# LIDO-HW_400_AccessoryInterfaces.net
KiCad netlist of a schematic drawn in Altium Designer
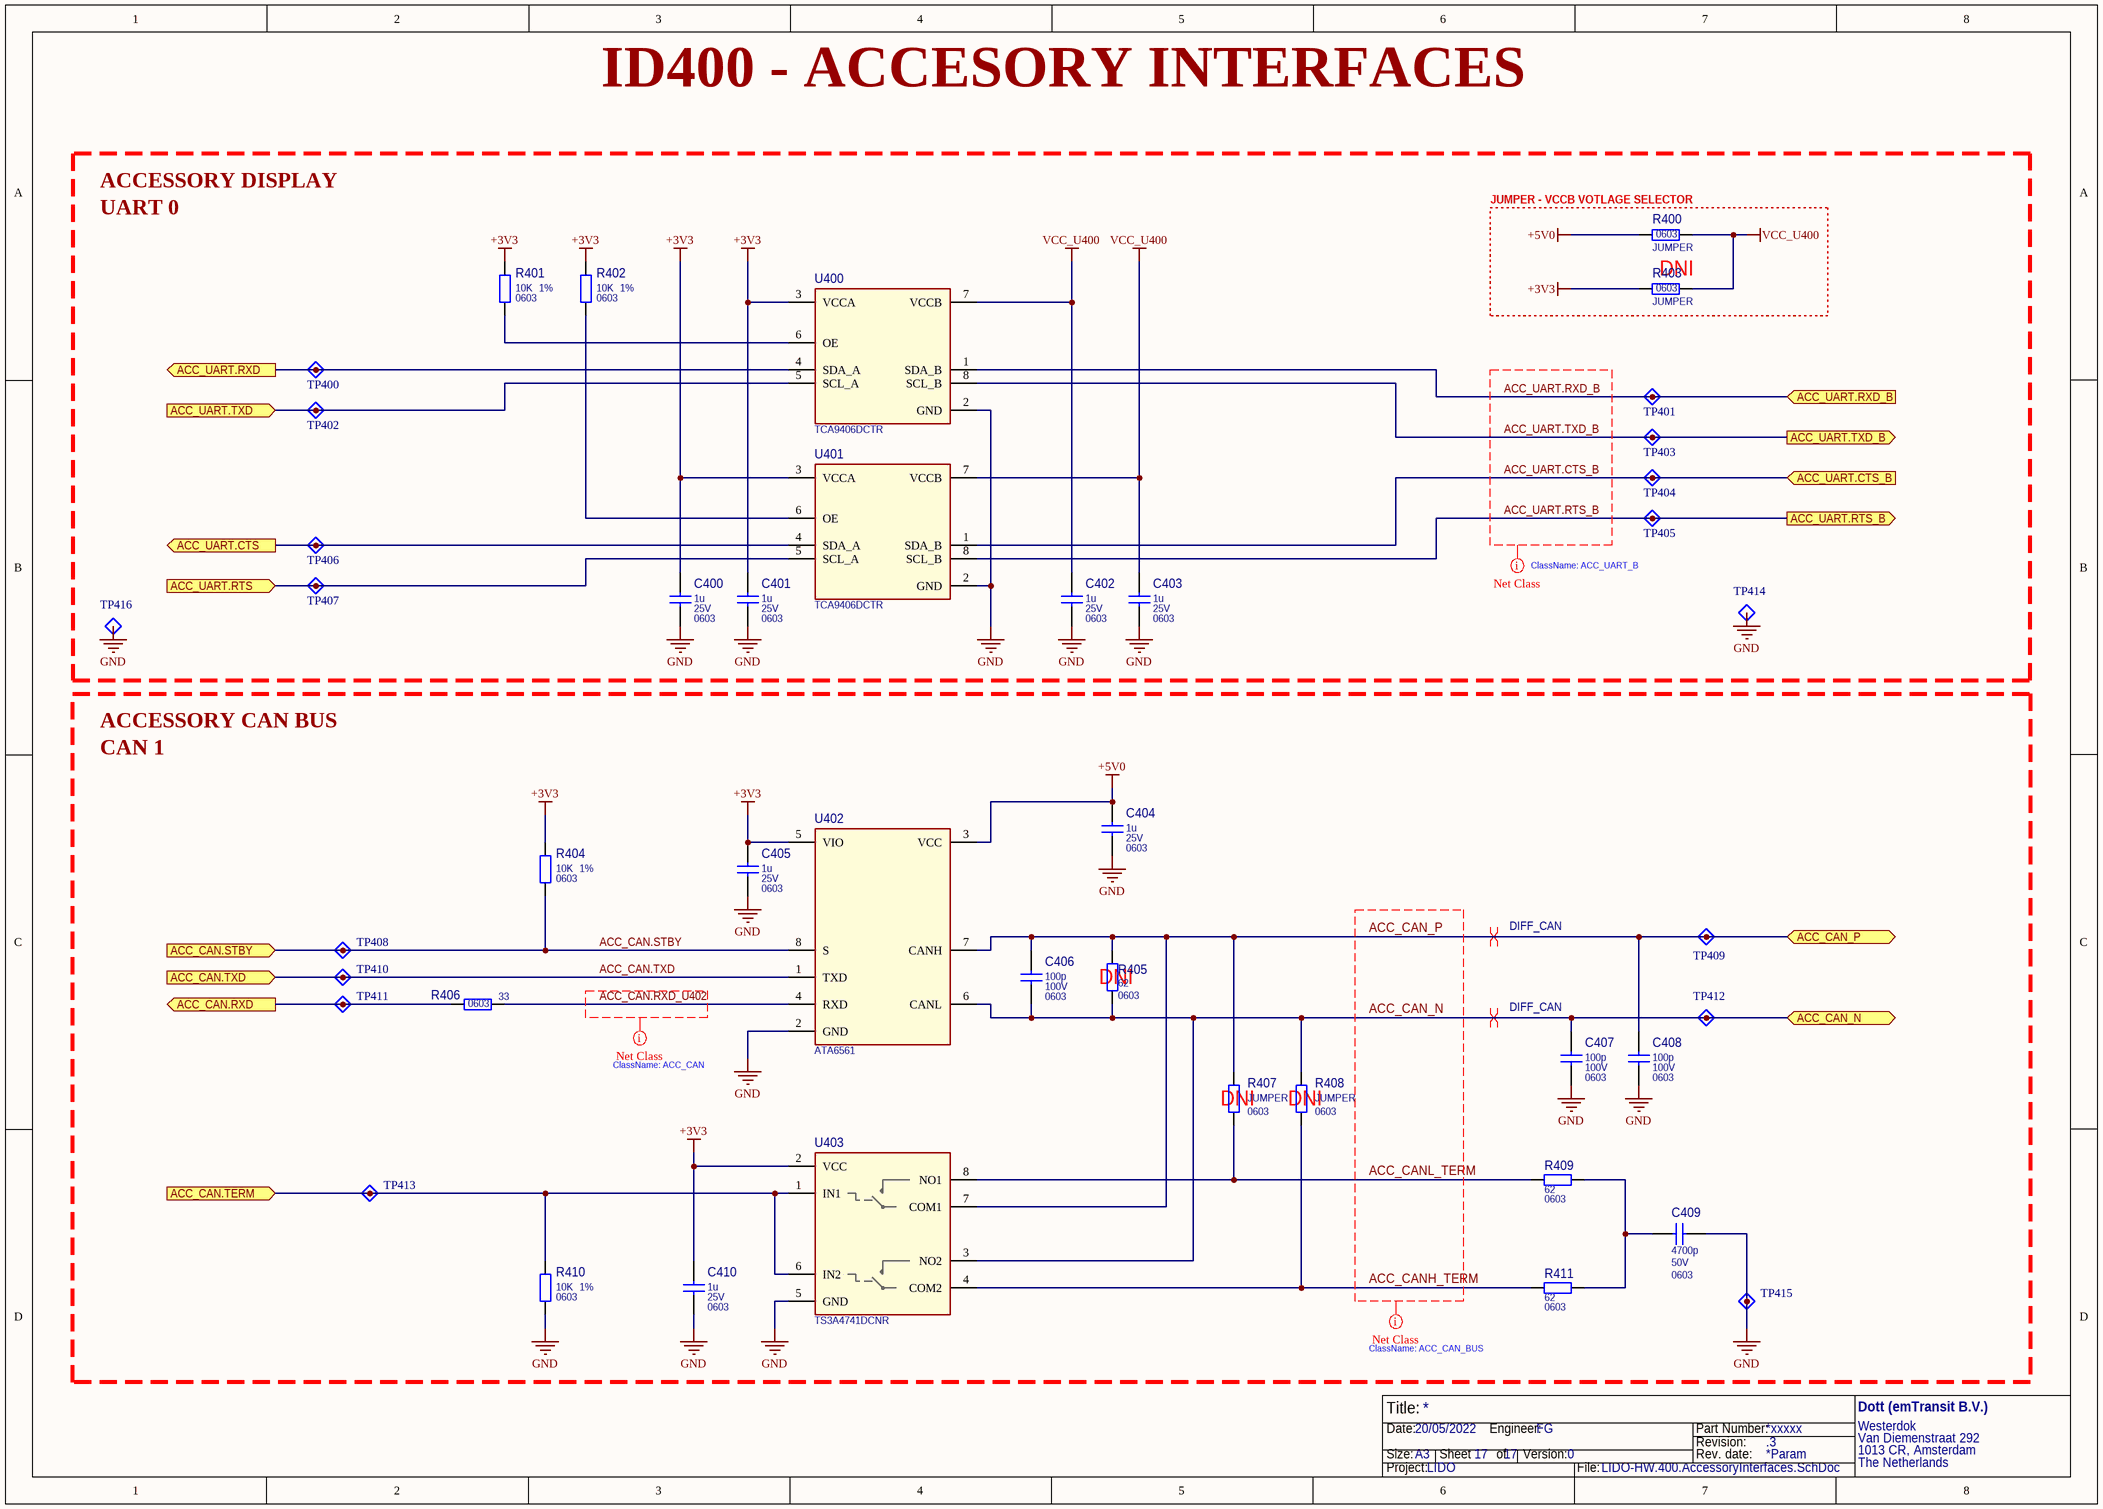
[diagram p0: LIDO-HW.400.AccessoryInterfaces.SchDoc]

(export (version "E")
  (design (tool "Eeschema 10.0.6"))
  (components
    (comp (ref "C400")
      (value "1u")
      (footprint "CAP_0603_1608X90-N_MURATA_A")
      (description "CAP CER 1UF 25V X7R 0603")
      (fields
        (field (name "MANUFACTURER PART NUMBER") "CGA3E1X7R1E105M080AE")
        (field (name "MANUFACTURER") "TDK Corporation")
        (field (name "PART VALUE 2") "25V")
        (field (name "PART PACKAGE") "0603")
      )
      (libsource (lib "DB_Library") (part "Ceramic"))
    )
    (comp (ref "C401")
      (value "1u")
      (footprint "CAP_0603_1608X90-N_MURATA_A")
      (description "CAP CER 1UF 25V X7R 0603")
      (fields
        (field (name "MANUFACTURER PART NUMBER") "CGA3E1X7R1E105M080AE")
        (field (name "MANUFACTURER") "TDK Corporation")
        (field (name "PART VALUE 2") "25V")
        (field (name "PART PACKAGE") "0603")
      )
      (libsource (lib "DB_Library") (part "Ceramic"))
    )
    (comp (ref "C402")
      (value "1u")
      (footprint "CAP_0603_1608X90-N_MURATA_A")
      (description "CAP CER 1UF 25V X7R 0603")
      (fields
        (field (name "MANUFACTURER PART NUMBER") "CGA3E1X7R1E105M080AE")
        (field (name "MANUFACTURER") "TDK Corporation")
        (field (name "PART VALUE 2") "25V")
        (field (name "PART PACKAGE") "0603")
      )
      (libsource (lib "DB_Library") (part "Ceramic"))
    )
    (comp (ref "C403")
      (value "1u")
      (footprint "CAP_0603_1608X90-N_MURATA_A")
      (description "CAP CER 1UF 25V X7R 0603")
      (fields
        (field (name "MANUFACTURER PART NUMBER") "CGA3E1X7R1E105M080AE")
        (field (name "MANUFACTURER") "TDK Corporation")
        (field (name "PART VALUE 2") "25V")
        (field (name "PART PACKAGE") "0603")
      )
      (libsource (lib "DB_Library") (part "Ceramic"))
    )
    (comp (ref "C404")
      (value "1u")
      (footprint "CAP_0603_1608X90-N_MURATA_A")
      (description "CAP CER 1UF 25V X7R 0603")
      (fields
        (field (name "MANUFACTURER PART NUMBER") "CGA3E1X7R1E105M080AE")
        (field (name "MANUFACTURER") "TDK Corporation")
        (field (name "PART VALUE 2") "25V")
        (field (name "PART PACKAGE") "0603")
      )
      (libsource (lib "DB_Library") (part "Ceramic"))
    )
    (comp (ref "C405")
      (value "1u")
      (footprint "CAP_0603_1608X90-N_MURATA_A")
      (description "CAP CER 1UF 25V X7R 0603")
      (fields
        (field (name "MANUFACTURER PART NUMBER") "CGA3E1X7R1E105M080AE")
        (field (name "MANUFACTURER") "TDK Corporation")
        (field (name "PART VALUE 2") "25V")
        (field (name "PART PACKAGE") "0603")
      )
      (libsource (lib "DB_Library") (part "Ceramic"))
    )
    (comp (ref "C406")
      (value "100p")
      (footprint "CAP_0603_1608X90-N_MURATA_A")
      (description "CAP CER 100PF 100V C0G 0603")
      (fields
        (field (name "MANUFACTURER PART NUMBER") "CGA3E2C0G2A101J080AA")
        (field (name "MANUFACTURER") "TDK Corporation")
        (field (name "PART VALUE 2") "100V")
        (field (name "PART PACKAGE") "0603")
      )
      (libsource (lib "DB_Library") (part "Ceramic"))
    )
    (comp (ref "C407")
      (value "100p")
      (footprint "CAP_0603_1608X90-N_MURATA_A")
      (description "CAP CER 100PF 100V C0G 0603")
      (fields
        (field (name "MANUFACTURER PART NUMBER") "CGA3E2C0G2A101J080AA")
        (field (name "MANUFACTURER") "TDK Corporation")
        (field (name "PART VALUE 2") "100V")
        (field (name "PART PACKAGE") "0603")
      )
      (libsource (lib "DB_Library") (part "Ceramic"))
    )
    (comp (ref "C408")
      (value "100p")
      (footprint "CAP_0603_1608X90-N_MURATA_A")
      (description "CAP CER 100PF 100V C0G 0603")
      (fields
        (field (name "MANUFACTURER PART NUMBER") "CGA3E2C0G2A101J080AA")
        (field (name "MANUFACTURER") "TDK Corporation")
        (field (name "PART VALUE 2") "100V")
        (field (name "PART PACKAGE") "0603")
      )
      (libsource (lib "DB_Library") (part "Ceramic"))
    )
    (comp (ref "C409")
      (value "4700p")
      (footprint "CAP_0603_1608X90-N_MURATA_A")
      (description "CAP CER 4700PF 50V X7R 0603")
      (fields
        (field (name "MANUFACTURER PART NUMBER") "CGA3E2X7R1H472K080AA")
        (field (name "MANUFACTURER") "TDK Corporation")
        (field (name "PART VALUE 2") "50V")
        (field (name "PART PACKAGE") "0603")
      )
      (libsource (lib "DB_Library") (part "Ceramic"))
    )
    (comp (ref "C410")
      (value "1u")
      (footprint "CAP_0603_1608X90-N_MURATA_A")
      (description "CAP CER 1UF 25V X7R 0603")
      (fields
        (field (name "MANUFACTURER PART NUMBER") "CGA3E1X7R1E105M080AE")
        (field (name "MANUFACTURER") "TDK Corporation")
        (field (name "PART VALUE 2") "25V")
        (field (name "PART PACKAGE") "0603")
      )
      (libsource (lib "DB_Library") (part "Ceramic"))
    )
    (comp (ref "R400")
      (value "JUMPER")
      (footprint "RES_0603_1608X60-N_YAGEO_A")
      (description "RES 0 OHM JUMPER 1/10W 0603")
      (fields
        (field (name "MANUFACTURER PART NUMBER") "RC0603JR-070RL")
        (field (name "MANUFACTURER") "YAGEO")
        (field (name "PART PACKAGE") "0603")
      )
      (libsource (lib "") (part "Resistor_1"))
    )
    (comp (ref "R401")
      (value "10K")
      (footprint "RES_0603_1608X60-N_YAGEO_A")
      (description "RES 10K OHM 1% 1/10W 0603")
      (fields
        (field (name "MANUFACTURER PART NUMBER") "RC0603FR-0710KL")
        (field (name "MANUFACTURER") "YAGEO")
        (field (name "PART VALUE 2") "1%")
        (field (name "PART PACKAGE") "0603")
      )
      (libsource (lib "DB_Library") (part "Resistor"))
    )
    (comp (ref "R402")
      (value "10K")
      (footprint "RES_0603_1608X60-N_YAGEO_A")
      (description "RES 10K OHM 1% 1/10W 0603")
      (fields
        (field (name "MANUFACTURER PART NUMBER") "RC0603FR-0710KL")
        (field (name "MANUFACTURER") "YAGEO")
        (field (name "PART VALUE 2") "1%")
        (field (name "PART PACKAGE") "0603")
      )
      (libsource (lib "DB_Library") (part "Resistor"))
    )
    (comp (ref "R403")
      (value "JUMPER")
      (footprint "RES_0603_1608X60-N_YAGEO_A")
      (description "RES 0 OHM JUMPER 1/10W 0603")
      (fields
        (field (name "MANUFACTURER PART NUMBER") "RC0603JR-070RL")
        (field (name "MANUFACTURER") "YAGEO")
        (field (name "PART PACKAGE") "0603")
      )
      (libsource (lib "") (part "Resistor_1"))
    )
    (comp (ref "R404")
      (value "10K")
      (footprint "RES_0603_1608X60-N_YAGEO_A")
      (description "RES 10K OHM 1% 1/10W 0603")
      (fields
        (field (name "MANUFACTURER PART NUMBER") "RC0603FR-0710KL")
        (field (name "MANUFACTURER") "YAGEO")
        (field (name "PART VALUE 2") "1%")
        (field (name "PART PACKAGE") "0603")
      )
      (libsource (lib "DB_Library") (part "Resistor"))
    )
    (comp (ref "R405")
      (value "62")
      (footprint "RES_0603_1608X60-N_YAGEO_A")
      (description "RES SMD 62 OHM 1% 1/10W 0603")
      (fields
        (field (name "MANUFACTURER PART NUMBER") "ERJ-3EKF62R0V")
        (field (name "MANUFACTURER") "Panasonic Electronic Components")
        (field (name "PART PACKAGE") "0603")
      )
      (libsource (lib "DB_Library") (part "Resistor"))
    )
    (comp (ref "R406")
      (value "33")
      (footprint "RES_0603_1608X60-N_YAGEO_A")
      (description "RES 33 OHM 5% 1/10W 0603")
      (fields
        (field (name "MANUFACTURER PART NUMBER") "RC0603JR-0733RL")
        (field (name "MANUFACTURER") "YAGEO")
        (field (name "PART PACKAGE") "0603")
      )
      (libsource (lib "") (part "Resistor_1"))
    )
    (comp (ref "R407")
      (value "JUMPER")
      (footprint "RES_0603_1608X60-N_YAGEO_A")
      (description "RES 0 OHM JUMPER 1/10W 0603")
      (fields
        (field (name "MANUFACTURER PART NUMBER") "RC0603JR-070RL")
        (field (name "MANUFACTURER") "YAGEO")
        (field (name "PART PACKAGE") "0603")
      )
      (libsource (lib "DB_Library") (part "Resistor"))
    )
    (comp (ref "R408")
      (value "JUMPER")
      (footprint "RES_0603_1608X60-N_YAGEO_A")
      (description "RES 0 OHM JUMPER 1/10W 0603")
      (fields
        (field (name "MANUFACTURER PART NUMBER") "RC0603JR-070RL")
        (field (name "MANUFACTURER") "YAGEO")
        (field (name "PART PACKAGE") "0603")
      )
      (libsource (lib "DB_Library") (part "Resistor"))
    )
    (comp (ref "R409")
      (value "62")
      (footprint "RES_0603_1608X60-N_YAGEO_A")
      (description "RES SMD 62 OHM 1% 1/10W 0603")
      (fields
        (field (name "MANUFACTURER PART NUMBER") "ERJ-3EKF62R0V")
        (field (name "MANUFACTURER") "Panasonic Electronic Components")
        (field (name "PART PACKAGE") "0603")
      )
      (libsource (lib "") (part "Resistor_1"))
    )
    (comp (ref "R410")
      (value "10K")
      (footprint "RES_0603_1608X60-N_YAGEO_A")
      (description "RES 10K OHM 1% 1/10W 0603")
      (fields
        (field (name "MANUFACTURER PART NUMBER") "RC0603FR-0710KL")
        (field (name "MANUFACTURER") "YAGEO")
        (field (name "PART VALUE 2") "1%")
        (field (name "PART PACKAGE") "0603")
      )
      (libsource (lib "DB_Library") (part "Resistor"))
    )
    (comp (ref "R411")
      (value "62")
      (footprint "RES_0603_1608X60-N_YAGEO_A")
      (description "RES SMD 62 OHM 1% 1/10W 0603")
      (fields
        (field (name "MANUFACTURER PART NUMBER") "ERJ-3EKF62R0V")
        (field (name "MANUFACTURER") "Panasonic Electronic Components")
        (field (name "PART PACKAGE") "0603")
      )
      (libsource (lib "") (part "Resistor_1"))
    )
    (comp (ref "TP400")
      (value "TestPoint_A")
      (footprint "TESTPOINT_1D_A")
      (description "Pad Diamater 1mm")
      (fields (field (name "PART") "Test Point 1D A") (field (name "OBSOLETE PART") "False"))
      (libsource (lib "DB_Library") (part "TestPoint_A"))
    )
    (comp (ref "TP401")
      (value "TestPoint_A")
      (footprint "TESTPOINT_1D_A")
      (description "Pad Diamater 1mm")
      (fields (field (name "PART") "Test Point 1D A") (field (name "OBSOLETE PART") "False"))
      (libsource (lib "DB_Library") (part "TestPoint_A"))
    )
    (comp (ref "TP402")
      (value "TestPoint_A")
      (footprint "TESTPOINT_1D_A")
      (description "Pad Diamater 1mm")
      (fields (field (name "PART") "Test Point 1D A") (field (name "OBSOLETE PART") "False"))
      (libsource (lib "DB_Library") (part "TestPoint_A"))
    )
    (comp (ref "TP403")
      (value "TestPoint_A")
      (footprint "TESTPOINT_1D_A")
      (description "Pad Diamater 1mm")
      (fields (field (name "PART") "Test Point 1D A") (field (name "OBSOLETE PART") "False"))
      (libsource (lib "DB_Library") (part "TestPoint_A"))
    )
    (comp (ref "TP404")
      (value "TestPoint_A")
      (footprint "TESTPOINT_1D_A")
      (description "Pad Diamater 1mm")
      (fields (field (name "PART") "Test Point 1D A") (field (name "OBSOLETE PART") "False"))
      (libsource (lib "DB_Library") (part "TestPoint_A"))
    )
    (comp (ref "TP405")
      (value "TestPoint_A")
      (footprint "TESTPOINT_1D_A")
      (description "Pad Diamater 1mm")
      (fields (field (name "PART") "Test Point 1D A") (field (name "OBSOLETE PART") "False"))
      (libsource (lib "DB_Library") (part "TestPoint_A"))
    )
    (comp (ref "TP406")
      (value "TestPoint_A")
      (footprint "TESTPOINT_1D_A")
      (description "Pad Diamater 1mm")
      (fields (field (name "PART") "Test Point 1D A") (field (name "OBSOLETE PART") "False"))
      (libsource (lib "DB_Library") (part "TestPoint_A"))
    )
    (comp (ref "TP407")
      (value "TestPoint_A")
      (footprint "TESTPOINT_1D_A")
      (description "Pad Diamater 1mm")
      (fields (field (name "PART") "Test Point 1D A") (field (name "OBSOLETE PART") "False"))
      (libsource (lib "DB_Library") (part "TestPoint_A"))
    )
    (comp (ref "TP408")
      (value "TestPoint_A")
      (footprint "TESTPOINT_1D_A")
      (description "Pad Diamater 1mm")
      (fields (field (name "PART") "Test Point 1D A") (field (name "OBSOLETE PART") "False"))
      (libsource (lib "DB_Library") (part "TestPoint_A"))
    )
    (comp (ref "TP409")
      (value "TestPoint_A")
      (footprint "TESTPOINT_1D_A")
      (description "Pad Diamater 1mm")
      (fields (field (name "PART") "Test Point 1D A") (field (name "OBSOLETE PART") "False"))
      (libsource (lib "DB_Library") (part "TestPoint_A"))
    )
    (comp (ref "TP410")
      (value "TestPoint_A")
      (footprint "TESTPOINT_1D_A")
      (description "Pad Diamater 1mm")
      (fields (field (name "PART") "Test Point 1D A") (field (name "OBSOLETE PART") "False"))
      (libsource (lib "DB_Library") (part "TestPoint_A"))
    )
    (comp (ref "TP411")
      (value "TestPoint_A")
      (footprint "TESTPOINT_1D_A")
      (description "Pad Diamater 1mm")
      (fields (field (name "PART") "Test Point 1D A") (field (name "OBSOLETE PART") "False"))
      (libsource (lib "DB_Library") (part "TestPoint_A"))
    )
    (comp (ref "TP412")
      (value "TestPoint_A")
      (footprint "TESTPOINT_1D_A")
      (description "Pad Diamater 1mm")
      (fields (field (name "PART") "Test Point 1D A") (field (name "OBSOLETE PART") "False"))
      (libsource (lib "DB_Library") (part "TestPoint_A"))
    )
    (comp (ref "TP413")
      (value "TestPoint_A")
      (footprint "TESTPOINT_1D_A")
      (description "Pad Diamater 1mm")
      (fields (field (name "PART") "Test Point 1D A") (field (name "OBSOLETE PART") "False"))
      (libsource (lib "DB_Library") (part "TestPoint_A"))
    )
    (comp (ref "TP414")
      (value "TestPoint_A")
      (footprint "TESTPOINT_1D_A")
      (description "Pad Diamater 1mm")
      (fields (field (name "PART") "Test Point 1D A") (field (name "OBSOLETE PART") "False"))
      (libsource (lib "DB_Library") (part "TestPoint_A"))
    )
    (comp (ref "TP415")
      (value "TestPoint_A")
      (footprint "TESTPOINT_1D_A")
      (description "Pad Diamater 1mm")
      (fields (field (name "PART") "Test Point 1D A") (field (name "OBSOLETE PART") "False"))
      (libsource (lib "DB_Library") (part "TestPoint_A"))
    )
    (comp (ref "TP416")
      (value "TestPoint_A")
      (footprint "TESTPOINT_1D_A")
      (description "Pad Diamater 1mm")
      (fields (field (name "PART") "Test Point 1D A") (field (name "OBSOLETE PART") "False"))
      (libsource (lib "DB_Library") (part "TestPoint_A"))
    )
    (comp (ref "U400")
      (value "TCA9406DCTR")
      (footprint "SSOP8P65_295X400X130L40X25-N_TI_A")
      (description "Voltage Level Translator Bidirectional 1 Circuit 2 Channel 24Mbps SM8")
      (fields (field (name "MANUFACTURER") "Texas Instruments") (field (name "OBSOLETE PART") "False"))
      (libsource (lib "DB_Library") (part "TCA9406_A"))
    )
    (comp (ref "U401")
      (value "TCA9406DCTR")
      (footprint "SSOP8P65_295X400X130L40X25-N_TI_A")
      (description "Voltage Level Translator Bidirectional 1 Circuit 2 Channel 24Mbps SM8")
      (fields (field (name "MANUFACTURER") "Texas Instruments") (field (name "OBSOLETE PART") "False"))
      (libsource (lib "DB_Library") (part "TCA9406_A"))
    )
    (comp (ref "U402")
      (value "ATA6561")
      (footprint "SOIC8P127_490X600X175L84X41-N_TI_A")
      (description "IC TRANSCEIVER 1/1 8SO")
      (fields
        (field (name "MANUFACTURER") "Microchip Technology")
        (field (name "MANUFACTURER PART NUMBER") "ATA6561-GAQW")
        (field (name "DESIGNER") "Matt Drazenovich")
        (field (name "REVIEWED") "Dekimo_07-07-2020")
      )
      (libsource (lib "DB_Library") (part "ATA6561_A"))
    )
    (comp (ref "U403")
      (value "TS3A4741DCNR")
      (footprint "SOT23-8P65_280X145L45-N_TI_A")
      (description "IC SWITCH DUAL SPST SOT23-8")
      (fields
        (field (name "MANUFACTURER") "Texas Instruments")
        (field (name "OBSOLETE PART") "False")
        (field (name "DESIGNER") "Matt Drazenovich")
        (field (name "REVIEWED") "Not Footprint")
      )
      (libsource (lib "DB_Library") (part "TS3A4741D_A"))
    )
  )
  (nets
    (net (code "1") (name "+3V3") (class "Default")
      (node (ref "C400") (pin "1") (pinfunction "1_1") (pintype "passive"))
      (node (ref "C401") (pin "1") (pinfunction "1_1") (pintype "passive"))
      (node (ref "C405") (pin "1") (pinfunction "1_1") (pintype "passive"))
      (node (ref "C410") (pin "1") (pinfunction "1_1") (pintype "passive"))
      (node (ref "R401") (pin "2") (pinfunction "2_2") (pintype "passive"))
      (node (ref "R402") (pin "2") (pinfunction "2_2") (pintype "passive"))
      (node (ref "R403") (pin "1") (pinfunction "1_1") (pintype "passive"))
      (node (ref "R404") (pin "2") (pinfunction "2_2") (pintype "passive"))
      (node (ref "U400") (pin "3") (pinfunction "VCCA_3") (pintype "power_in"))
      (node (ref "U401") (pin "3") (pinfunction "VCCA_3") (pintype "power_in"))
      (node (ref "U402") (pin "5") (pinfunction "VIO_5") (pintype "power_in"))
      (node (ref "U403") (pin "2") (pinfunction "VCC_2") (pintype "power_in"))
    )
    (net (code "2") (name "+5V0") (class "Default")
      (node (ref "C404") (pin "1") (pinfunction "1_1") (pintype "passive"))
      (node (ref "R400") (pin "1") (pinfunction "1_1") (pintype "passive"))
      (node (ref "U402") (pin "3") (pinfunction "VCC_3") (pintype "power_in"))
    )
    (net (code "3") (name "/ACC_CAN.RXD") (class "Default")
      (node (ref "R406") (pin "1") (pinfunction "1_1") (pintype "passive"))
      (node (ref "TP411") (pin "1") (pinfunction "TP_1") (pintype "passive"))
    )
    (net (code "4") (name "/ACC_CAN.RXD_U402") (class "Default")
      (node (ref "R406") (pin "2") (pinfunction "2_2") (pintype "passive"))
      (node (ref "U402") (pin "4") (pinfunction "RXD_4") (pintype "passive"))
    )
    (net (code "5") (name "/ACC_CAN.STBY") (class "Default")
      (node (ref "R404") (pin "1") (pinfunction "1_1") (pintype "passive"))
      (node (ref "TP408") (pin "1") (pinfunction "TP_1") (pintype "passive"))
      (node (ref "U402") (pin "8") (pinfunction "S_8") (pintype "passive"))
    )
    (net (code "6") (name "/ACC_CAN.TERM") (class "Default")
      (node (ref "R410") (pin "2") (pinfunction "2_2") (pintype "passive"))
      (node (ref "TP413") (pin "1") (pinfunction "TP_1") (pintype "passive"))
      (node (ref "U403") (pin "1") (pinfunction "IN1_1") (pintype "passive"))
      (node (ref "U403") (pin "6") (pinfunction "IN2_6") (pintype "passive"))
    )
    (net (code "7") (name "/ACC_CAN.TXD") (class "Default")
      (node (ref "TP410") (pin "1") (pinfunction "TP_1") (pintype "passive"))
      (node (ref "U402") (pin "1") (pinfunction "TXD_1") (pintype "passive"))
    )
    (net (code "8") (name "/ACC_CANH_TERM") (class "Default")
      (node (ref "R408") (pin "1") (pinfunction "1_1") (pintype "passive"))
      (node (ref "R411") (pin "1") (pinfunction "1_1") (pintype "passive"))
      (node (ref "U403") (pin "4") (pinfunction "COM2_4") (pintype "passive"))
    )
    (net (code "9") (name "/ACC_CANL_TERM") (class "Default")
      (node (ref "R407") (pin "1") (pinfunction "1_1") (pintype "passive"))
      (node (ref "R409") (pin "1") (pinfunction "1_1") (pintype "passive"))
      (node (ref "U403") (pin "8") (pinfunction "NO1_8") (pintype "passive"))
    )
    (net (code "10") (name "/ACC_CAN_N") (class "Default")
      (node (ref "C406") (pin "2") (pinfunction "2_2") (pintype "passive"))
      (node (ref "C407") (pin "1") (pinfunction "1_1") (pintype "passive"))
      (node (ref "R405") (pin "1") (pinfunction "1_1") (pintype "passive"))
      (node (ref "R408") (pin "2") (pinfunction "2_2") (pintype "passive"))
      (node (ref "TP412") (pin "1") (pinfunction "TP_1") (pintype "passive"))
      (node (ref "U402") (pin "6") (pinfunction "CANL_6") (pintype "passive"))
      (node (ref "U403") (pin "3") (pinfunction "NO2_3") (pintype "passive"))
    )
    (net (code "11") (name "/ACC_CAN_P") (class "Default")
      (node (ref "C406") (pin "1") (pinfunction "1_1") (pintype "passive"))
      (node (ref "C408") (pin "1") (pinfunction "1_1") (pintype "passive"))
      (node (ref "R405") (pin "2") (pinfunction "2_2") (pintype "passive"))
      (node (ref "R407") (pin "2") (pinfunction "2_2") (pintype "passive"))
      (node (ref "TP409") (pin "1") (pinfunction "TP_1") (pintype "passive"))
      (node (ref "U402") (pin "7") (pinfunction "CANH_7") (pintype "passive"))
      (node (ref "U403") (pin "7") (pinfunction "COM1_7") (pintype "passive"))
    )
    (net (code "12") (name "/ACC_UART.CTS") (class "Default")
      (node (ref "TP406") (pin "1") (pinfunction "TP_1") (pintype "passive"))
      (node (ref "U401") (pin "4") (pinfunction "SDA_A_4") (pintype "passive"))
    )
    (net (code "13") (name "/ACC_UART.CTS_B") (class "Default")
      (node (ref "TP404") (pin "1") (pinfunction "TP_1") (pintype "passive"))
      (node (ref "U401") (pin "1") (pinfunction "SDA_B_1") (pintype "passive"))
    )
    (net (code "14") (name "/ACC_UART.RTS") (class "Default")
      (node (ref "TP407") (pin "1") (pinfunction "TP_1") (pintype "passive"))
      (node (ref "U401") (pin "5") (pinfunction "SCL_A_5") (pintype "passive"))
    )
    (net (code "15") (name "/ACC_UART.RTS_B") (class "Default")
      (node (ref "TP405") (pin "1") (pinfunction "TP_1") (pintype "passive"))
      (node (ref "U401") (pin "8") (pinfunction "SCL_B_8") (pintype "passive"))
    )
    (net (code "16") (name "/ACC_UART.RXD") (class "Default")
      (node (ref "TP400") (pin "1") (pinfunction "TP_1") (pintype "passive"))
      (node (ref "U400") (pin "4") (pinfunction "SDA_A_4") (pintype "passive"))
    )
    (net (code "17") (name "/ACC_UART.RXD_B") (class "Default")
      (node (ref "TP401") (pin "1") (pinfunction "TP_1") (pintype "passive"))
      (node (ref "U400") (pin "1") (pinfunction "SDA_B_1") (pintype "passive"))
    )
    (net (code "18") (name "/ACC_UART.TXD") (class "Default")
      (node (ref "TP402") (pin "1") (pinfunction "TP_1") (pintype "passive"))
      (node (ref "U400") (pin "5") (pinfunction "SCL_A_5") (pintype "passive"))
    )
    (net (code "19") (name "/ACC_UART.TXD_B") (class "Default")
      (node (ref "TP403") (pin "1") (pinfunction "TP_1") (pintype "passive"))
      (node (ref "U400") (pin "8") (pinfunction "SCL_B_8") (pintype "passive"))
    )
    (net (code "20") (name "GND") (class "Default")
      (node (ref "C400") (pin "2") (pinfunction "2_2") (pintype "passive"))
      (node (ref "C401") (pin "2") (pinfunction "2_2") (pintype "passive"))
      (node (ref "C402") (pin "2") (pinfunction "2_2") (pintype "passive"))
      (node (ref "C403") (pin "2") (pinfunction "2_2") (pintype "passive"))
      (node (ref "C404") (pin "2") (pinfunction "2_2") (pintype "passive"))
      (node (ref "C405") (pin "2") (pinfunction "2_2") (pintype "passive"))
      (node (ref "C407") (pin "2") (pinfunction "2_2") (pintype "passive"))
      (node (ref "C408") (pin "2") (pinfunction "2_2") (pintype "passive"))
      (node (ref "C409") (pin "2") (pinfunction "2_2") (pintype "passive"))
      (node (ref "C410") (pin "2") (pinfunction "2_2") (pintype "passive"))
      (node (ref "R410") (pin "1") (pinfunction "1_1") (pintype "passive"))
      (node (ref "TP414") (pin "1") (pinfunction "TP_1") (pintype "passive"))
      (node (ref "TP415") (pin "1") (pinfunction "TP_1") (pintype "passive"))
      (node (ref "TP416") (pin "1") (pinfunction "TP_1") (pintype "passive"))
      (node (ref "U400") (pin "2") (pinfunction "GND_2") (pintype "power_in"))
      (node (ref "U401") (pin "2") (pinfunction "GND_2") (pintype "power_in"))
      (node (ref "U402") (pin "2") (pinfunction "GND_2") (pintype "power_in"))
      (node (ref "U403") (pin "5") (pinfunction "GND_5") (pintype "power_in"))
    )
    (net (code "21") (name "Net-(C409-Pad1)") (class "Default")
      (node (ref "C409") (pin "1") (pinfunction "1_1") (pintype "passive"))
      (node (ref "R409") (pin "2") (pinfunction "2_2") (pintype "passive"))
      (node (ref "R411") (pin "2") (pinfunction "2_2") (pintype "passive"))
    )
    (net (code "22") (name "Net-(U400-OE)") (class "Default")
      (node (ref "R401") (pin "1") (pinfunction "1_1") (pintype "passive"))
      (node (ref "U400") (pin "6") (pinfunction "OE_6") (pintype "passive"))
    )
    (net (code "23") (name "Net-(U401-OE)") (class "Default")
      (node (ref "R402") (pin "1") (pinfunction "1_1") (pintype "passive"))
      (node (ref "U401") (pin "6") (pinfunction "OE_6") (pintype "passive"))
    )
    (net (code "24") (name "VCC_U400") (class "Default")
      (node (ref "C402") (pin "1") (pinfunction "1_1") (pintype "passive"))
      (node (ref "C403") (pin "1") (pinfunction "1_1") (pintype "passive"))
      (node (ref "R400") (pin "2") (pinfunction "2_2") (pintype "passive"))
      (node (ref "R403") (pin "2") (pinfunction "2_2") (pintype "passive"))
      (node (ref "U400") (pin "7") (pinfunction "VCCB_7") (pintype "power_in"))
      (node (ref "U401") (pin "7") (pinfunction "VCCB_7") (pintype "power_in"))
    )
  )
)
